# SparkFun_Micro_Color_Sensor_OPT4048.net
KiCad netlist of a schematic drawn in EAGLE
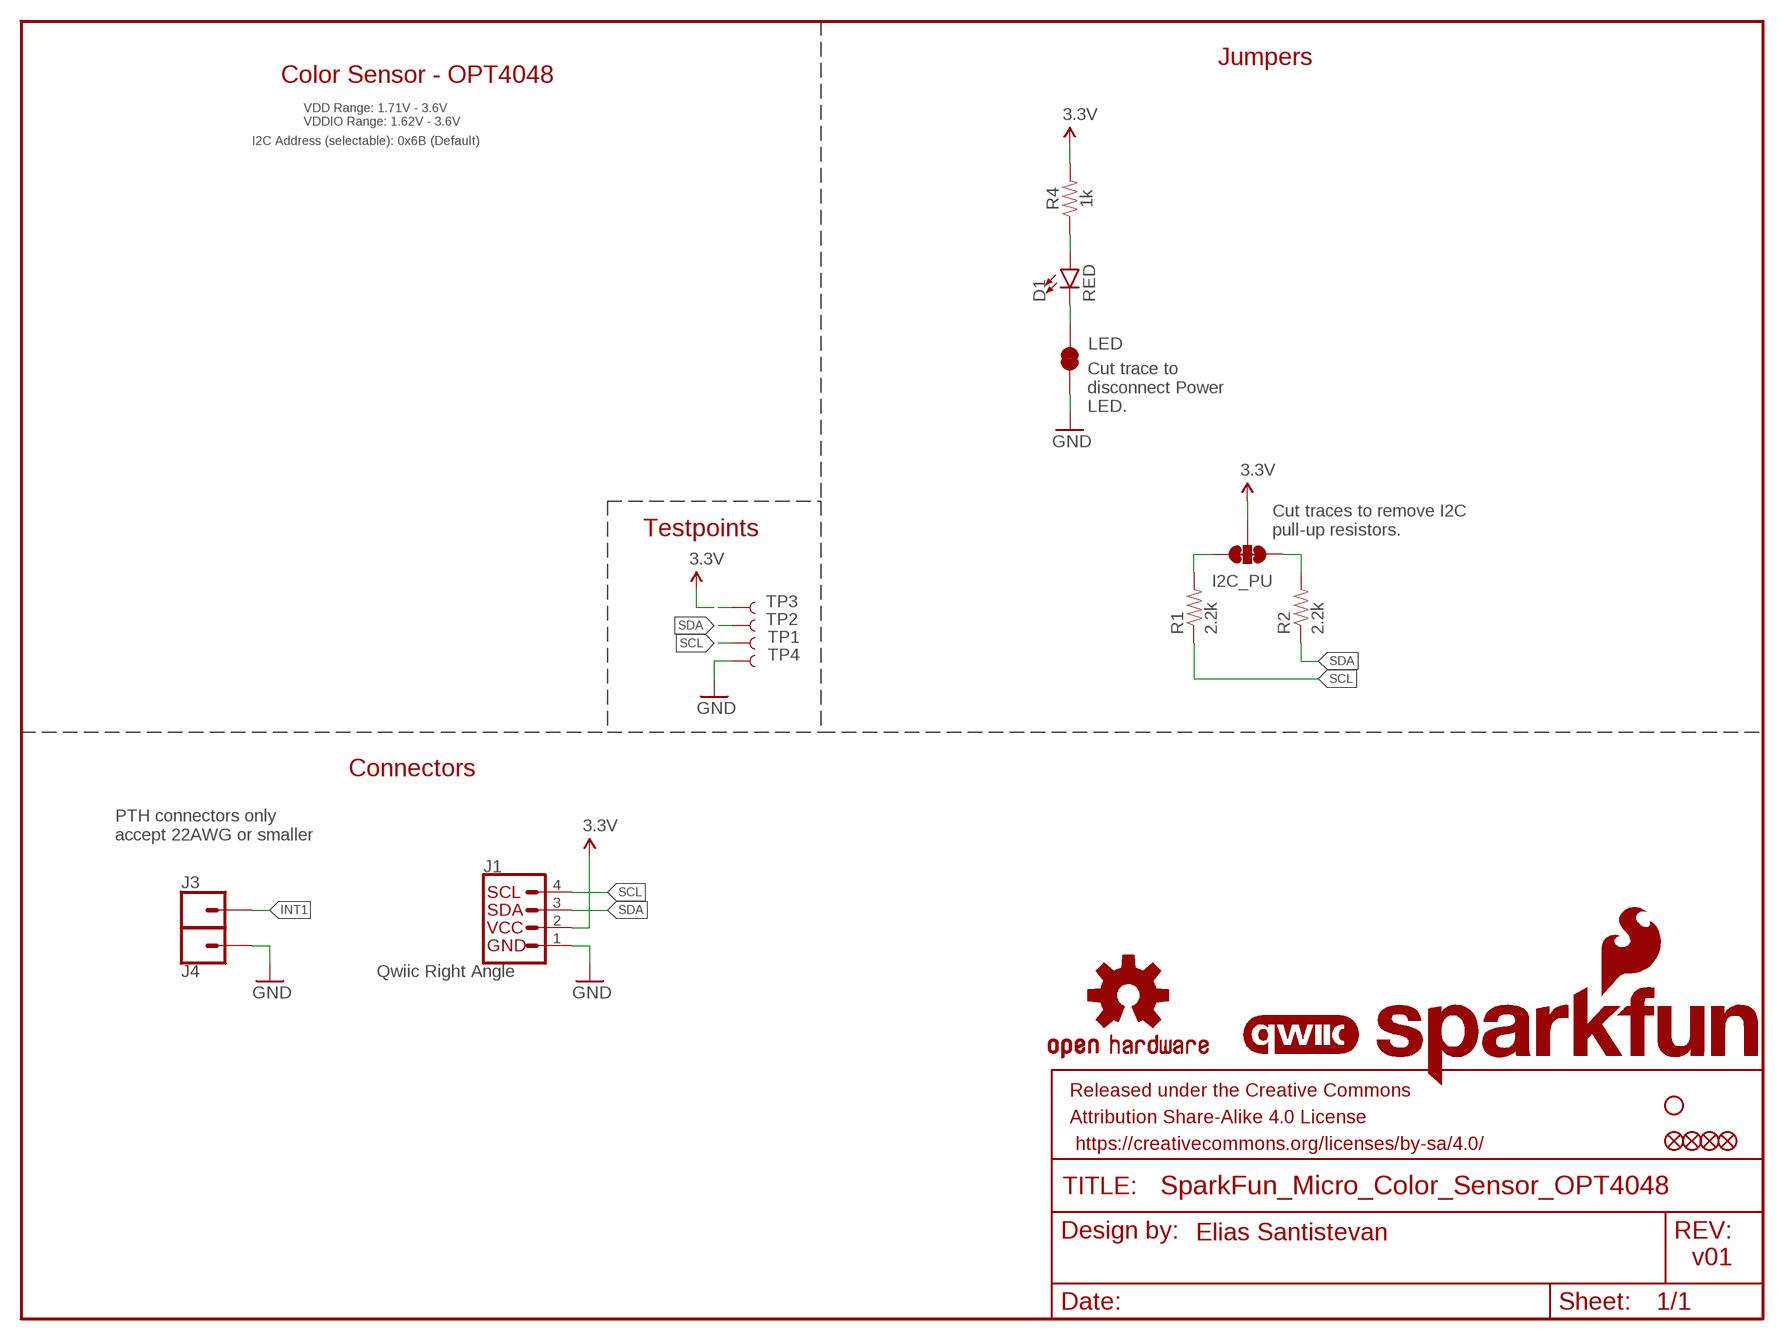
[diagram p0: schematic, sheet 1]

(export (version "E")
  (design (tool "Eeschema 10.0.6"))
  (components
    (comp (ref "D1")
      (value "RED")
      (footprint "eagle-import:LED-0402")
      (libsource (lib "eagle-import") (part "LED-RED_0402"))
    )
    (comp (ref "FD1")
      (value "FIDUCIALUFIDUCIAL")
      (footprint "eagle-import:FIDUCIAL-MICRO")
      (libsource (lib "eagle-import") (part "FIDUCIALUFIDUCIAL"))
    )
    (comp (ref "FD2")
      (value "FIDUCIALUFIDUCIAL")
      (footprint "eagle-import:FIDUCIAL-MICRO")
      (libsource (lib "eagle-import") (part "FIDUCIALUFIDUCIAL"))
    )
    (comp (ref "FID1")
      (value "FIDUCIALUFIDUCIAL")
      (footprint "eagle-import:FIDUCIAL-MICRO")
      (libsource (lib "eagle-import") (part "FIDUCIALUFIDUCIAL"))
    )
    (comp (ref "FID2")
      (value "FIDUCIALUFIDUCIAL")
      (footprint "eagle-import:FIDUCIAL-MICRO")
      (libsource (lib "eagle-import") (part "FIDUCIALUFIDUCIAL"))
    )
    (comp (ref "FRAME1")
      (value "FRAME-LETTER")
      (footprint "eagle-import:CREATIVE_COMMONS")
      (fields (field (name "DESIGNER") "Elias Santistevan"))
      (libsource (lib "eagle-import") (part "FRAME-LETTER"))
    )
    (comp (ref "I2C_PU")
      (value "S_MODE")
      (footprint "eagle-import:SMT-JUMPER_3_2-NC_TRACE_SILK")
      (libsource (lib "eagle-import") (part "JUMPER-SMT_3_2-NC_TRACE_SILK"))
    )
    (comp (ref "J1")
      (value "Qwiic Right Angle")
      (footprint "eagle-import:JST04_1MM_RA")
      (libsource (lib "eagle-import") (part "I2C_STANDARDQWIIC"))
    )
    (comp (ref "J3")
      (value "CONN_01_1MM")
      (footprint "eagle-import:1X01_1MM_NO_SILK")
      (libsource (lib "eagle-import") (part "CONN_01_1MM"))
    )
    (comp (ref "J4")
      (value "CONN_01_1MM")
      (footprint "eagle-import:1X01_1MM_NO_SILK")
      (libsource (lib "eagle-import") (part "CONN_01_1MM"))
    )
    (comp (ref "LED")
      (value "JUMPER-SMT_2_NC_TRACE_SILK")
      (footprint "eagle-import:SMT-JUMPER_2_NC_TRACE_SILK")
      (libsource (lib "eagle-import") (part "JUMPER-SMT_2_NC_TRACE_SILK"))
    )
    (comp (ref "LOGO1")
      (value "QWIIC_LOGO_3MM")
      (footprint "eagle-import:QWIIC_3MM")
      (libsource (lib "eagle-import") (part "QWIIC_LOGO_3MM"))
    )
    (comp (ref "LOGO2")
      (value "OSHW-LOGOMINI")
      (footprint "eagle-import:OSHW-LOGO-MINI")
      (libsource (lib "eagle-import") (part "OSHW-LOGOMINI"))
    )
    (comp (ref "LOGO3")
      (value "SFE_LOGO_NAME_FLAMEBLANK")
      (footprint "eagle-import:BLANK")
      (libsource (lib "eagle-import") (part "SFE_LOGO_NAME_FLAMEBLANK"))
    )
    (comp (ref "R1")
      (value "2.2k")
      (footprint "eagle-import:0402-TIGHT")
      (libsource (lib "eagle-import") (part "2.2KOHM-0402T-1/16W-1%"))
    )
    (comp (ref "R2")
      (value "2.2k")
      (footprint "eagle-import:0402-TIGHT")
      (libsource (lib "eagle-import") (part "2.2KOHM-0402T-1/16W-1%"))
    )
    (comp (ref "R4")
      (value "1k")
      (footprint "eagle-import:0402-TIGHT")
      (libsource (lib "eagle-import") (part "1KOHM-0402T-1/16W-1%"))
    )
    (comp (ref "STANDOFF1")
      (value "STAND-OFFTIGHT")
      (footprint "eagle-import:STAND-OFF-TIGHT")
      (libsource (lib "eagle-import") (part "STAND-OFFTIGHT"))
    )
    (comp (ref "TP1")
      (value "TEST-POINT3")
      (footprint "eagle-import:PAD.03X.03")
      (libsource (lib "eagle-import") (part "TEST-POINT3"))
    )
    (comp (ref "TP2")
      (value "TEST-POINT3")
      (footprint "eagle-import:PAD.03X.03")
      (libsource (lib "eagle-import") (part "TEST-POINT3"))
    )
    (comp (ref "TP3")
      (value "TEST-POINT3")
      (footprint "eagle-import:PAD.03X.03")
      (libsource (lib "eagle-import") (part "TEST-POINT3"))
    )
    (comp (ref "TP4")
      (value "TEST-POINT3")
      (footprint "eagle-import:PAD.03X.03")
      (libsource (lib "eagle-import") (part "TEST-POINT3"))
    )
  )
  (nets
    (net (code "1") (name "3.3V") (class "Default")
      (node (ref "I2C_PU") (pin "2") (pinfunction "2_2") (pintype "passive"))
      (node (ref "J1") (pin "2") (pinfunction "2_2") (pintype "power_in"))
      (node (ref "R4") (pin "2") (pinfunction "2_2") (pintype "passive"))
      (node (ref "TP3") (pin "1") (pinfunction "1_1") (pintype "bidirectional"))
    )
    (net (code "2") (name "GND") (class "Default")
      (node (ref "J1") (pin "1") (pinfunction "1_1") (pintype "power_in"))
      (node (ref "J4") (pin "1") (pinfunction "1_1") (pintype "passive"))
      (node (ref "LED") (pin "1") (pinfunction "1_1") (pintype "passive"))
      (node (ref "TP4") (pin "1") (pinfunction "1_1") (pintype "bidirectional"))
    )
    (net (code "3") (name "INT1") (class "Default")
      (node (ref "J3") (pin "1") (pinfunction "1_1") (pintype "passive"))
    )
    (net (code "4") (name "Net-(D1-PadA)") (class "Default")
      (node (ref "D1") (pin "A") (pinfunction "A_A") (pintype "passive"))
      (node (ref "R4") (pin "1") (pinfunction "1_1") (pintype "passive"))
    )
    (net (code "5") (name "Net-(D1-PadC)") (class "Default")
      (node (ref "D1") (pin "C") (pinfunction "C_C") (pintype "passive"))
      (node (ref "LED") (pin "2") (pinfunction "2_2") (pintype "passive"))
    )
    (net (code "6") (name "Net-(I2C_PU-Pad1)") (class "Default")
      (node (ref "I2C_PU") (pin "1") (pinfunction "1_1") (pintype "passive"))
      (node (ref "R1") (pin "2") (pinfunction "2_2") (pintype "passive"))
    )
    (net (code "7") (name "Net-(I2C_PU-Pad3)") (class "Default")
      (node (ref "I2C_PU") (pin "3") (pinfunction "3_3") (pintype "passive"))
      (node (ref "R2") (pin "2") (pinfunction "2_2") (pintype "passive"))
    )
    (net (code "8") (name "SCL") (class "Default")
      (node (ref "J1") (pin "4") (pinfunction "4_4") (pintype "passive"))
      (node (ref "R1") (pin "1") (pinfunction "1_1") (pintype "passive"))
      (node (ref "TP1") (pin "1") (pinfunction "1_1") (pintype "bidirectional"))
    )
    (net (code "9") (name "SDA") (class "Default")
      (node (ref "J1") (pin "3") (pinfunction "3_3") (pintype "passive"))
      (node (ref "R2") (pin "1") (pinfunction "1_1") (pintype "passive"))
      (node (ref "TP2") (pin "1") (pinfunction "1_1") (pintype "bidirectional"))
    )
  )
)
